# SerialComm.net
KiCad netlist of a schematic drawn in Altium Designer
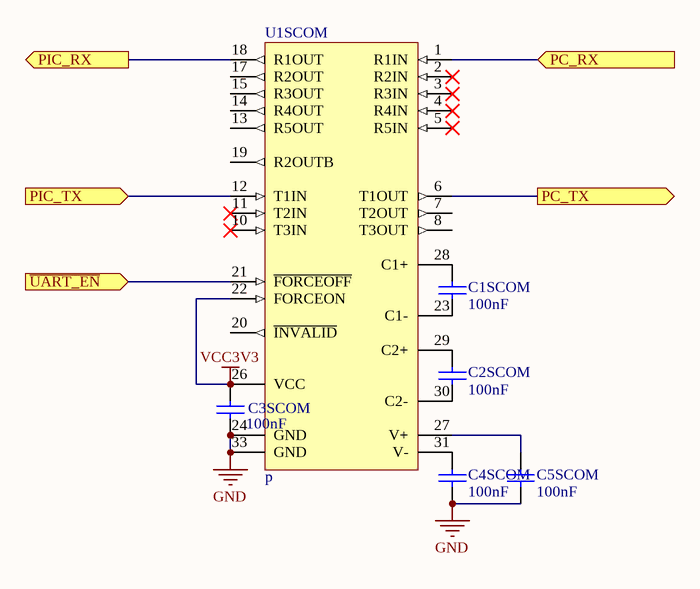
[diagram p0: SerialComm.SchDoc]

(export (version "E")
  (design (tool "Eeschema 10.0.6"))
  (components
    (comp (ref "C1SCOM")
      (value "100nF")
      (footprint "CC1608-0603")
      (description "Capacitor")
      (fields (field (name "MANUFACTURER") "Taiyo Yuden") (field (name "Comment") "UMK107BJ104KA-T"))
      (libsource (lib "Comp") (part "Cap"))
    )
    (comp (ref "C2SCOM")
      (value "100nF")
      (footprint "CC1608-0603")
      (description "Capacitor")
      (fields (field (name "MANUFACTURER") "Taiyo Yuden") (field (name "Comment") "UMK107BJ104KA-T"))
      (libsource (lib "Comp") (part "Cap"))
    )
    (comp (ref "C3SCOM")
      (value "100nF")
      (footprint "CC1608-0603")
      (description "Capacitor")
      (fields (field (name "MANUFACTURER") "Taiyo Yuden") (field (name "Comment") "UMK107BJ104KA-T"))
      (libsource (lib "Comp") (part "Cap"))
    )
    (comp (ref "C4SCOM")
      (value "100nF")
      (footprint "CC1608-0603")
      (description "Capacitor")
      (fields (field (name "MANUFACTURER") "Taiyo Yuden") (field (name "Comment") "UMK107BJ104KA-T"))
      (libsource (lib "Comp") (part "Cap"))
    )
    (comp (ref "C5SCOM")
      (value "100nF")
      (footprint "CC1608-0603")
      (description "Capacitor")
      (fields (field (name "MANUFACTURER") "Taiyo Yuden") (field (name "Comment") "UMK107BJ104KA-T"))
      (libsource (lib "Comp") (part "Cap"))
    )
    (comp (ref "U1SCOM")
      (value "p")
      (footprint "Footprints:QFN5X5-32")
      (description "RS232 Transceiver")
      (fields (field (name "MANUFACTURER") "Texas Instruments"))
      (libsource (lib "Comp") (part "MAX3243E_SMALL"))
    )
  )
  (nets
    (net (code "1") (name "/PC_RX") (class "Default")
      (node (ref "U1SCOM") (pin "1") (pinfunction "R1IN_1") (pintype "input"))
    )
    (net (code "2") (name "/PC_TX") (class "Default")
      (node (ref "U1SCOM") (pin "6") (pinfunction "T1OUT_6") (pintype "output"))
    )
    (net (code "3") (name "/PIC_RX") (class "Default")
      (node (ref "U1SCOM") (pin "18") (pinfunction "R1OUT_18") (pintype "output"))
    )
    (net (code "4") (name "/PIC_TX") (class "Default")
      (node (ref "U1SCOM") (pin "12") (pinfunction "T1IN_12") (pintype "input"))
    )
    (net (code "5") (name "/~{UART_EN}") (class "Default")
      (node (ref "U1SCOM") (pin "21") (pinfunction "~{FORCEOFF}_21") (pintype "input"))
    )
    (net (code "6") (name "GND") (class "Default")
      (node (ref "C3SCOM") (pin "2") (pinfunction "2_2") (pintype "passive"))
      (node (ref "C4SCOM") (pin "2") (pinfunction "2_2") (pintype "passive"))
      (node (ref "C5SCOM") (pin "2") (pinfunction "2_2") (pintype "passive"))
      (node (ref "U1SCOM") (pin "24") (pinfunction "GND_24") (pintype "power_in"))
      (node (ref "U1SCOM") (pin "33") (pinfunction "GND_33") (pintype "power_in"))
    )
    (net (code "7") (name "Net-(U1SCOM-C1+)") (class "Default")
      (node (ref "C1SCOM") (pin "1") (pinfunction "1_1") (pintype "passive"))
      (node (ref "U1SCOM") (pin "28") (pinfunction "C1+_28") (pintype "passive"))
    )
    (net (code "8") (name "Net-(U1SCOM-C1-)") (class "Default")
      (node (ref "C1SCOM") (pin "2") (pinfunction "2_2") (pintype "passive"))
      (node (ref "U1SCOM") (pin "23") (pinfunction "C1-_23") (pintype "passive"))
    )
    (net (code "9") (name "Net-(U1SCOM-C2+)") (class "Default")
      (node (ref "C2SCOM") (pin "1") (pinfunction "1_1") (pintype "passive"))
      (node (ref "U1SCOM") (pin "29") (pinfunction "C2+_29") (pintype "passive"))
    )
    (net (code "10") (name "Net-(U1SCOM-C2-)") (class "Default")
      (node (ref "C2SCOM") (pin "2") (pinfunction "2_2") (pintype "passive"))
      (node (ref "U1SCOM") (pin "30") (pinfunction "C2-_30") (pintype "passive"))
    )
    (net (code "11") (name "Net-(U1SCOM-V+)") (class "Default")
      (node (ref "C5SCOM") (pin "1") (pinfunction "1_1") (pintype "passive"))
      (node (ref "U1SCOM") (pin "27") (pinfunction "V+_27") (pintype "passive"))
    )
    (net (code "12") (name "Net-(U1SCOM-V-)") (class "Default")
      (node (ref "C4SCOM") (pin "1") (pinfunction "1_1") (pintype "passive"))
      (node (ref "U1SCOM") (pin "31") (pinfunction "V-_31") (pintype "passive"))
    )
    (net (code "13") (name "VCC3V3") (class "Default")
      (node (ref "C3SCOM") (pin "1") (pinfunction "1_1") (pintype "passive"))
      (node (ref "U1SCOM") (pin "22") (pinfunction "FORCEON_22") (pintype "input"))
      (node (ref "U1SCOM") (pin "26") (pinfunction "VCC_26") (pintype "power_in"))
    )
    (net (code "14") (name "unconnected-(U1SCOM-R2IN-Pad2)") (class "Default")
      (node (ref "U1SCOM") (pin "2") (pinfunction "R2IN_2") (pintype "input+no_connect"))
    )
    (net (code "15") (name "unconnected-(U1SCOM-R2OUT-Pad17)") (class "Default")
      (node (ref "U1SCOM") (pin "17") (pinfunction "R2OUT_17") (pintype "output"))
    )
    (net (code "16") (name "unconnected-(U1SCOM-R2OUTB-Pad19)") (class "Default")
      (node (ref "U1SCOM") (pin "19") (pinfunction "R2OUTB_19") (pintype "output"))
    )
    (net (code "17") (name "unconnected-(U1SCOM-R3IN-Pad3)") (class "Default")
      (node (ref "U1SCOM") (pin "3") (pinfunction "R3IN_3") (pintype "input+no_connect"))
    )
    (net (code "18") (name "unconnected-(U1SCOM-R3OUT-Pad15)") (class "Default")
      (node (ref "U1SCOM") (pin "15") (pinfunction "R3OUT_15") (pintype "output"))
    )
    (net (code "19") (name "unconnected-(U1SCOM-R4IN-Pad4)") (class "Default")
      (node (ref "U1SCOM") (pin "4") (pinfunction "R4IN_4") (pintype "input+no_connect"))
    )
    (net (code "20") (name "unconnected-(U1SCOM-R4OUT-Pad14)") (class "Default")
      (node (ref "U1SCOM") (pin "14") (pinfunction "R4OUT_14") (pintype "output"))
    )
    (net (code "21") (name "unconnected-(U1SCOM-R5IN-Pad5)") (class "Default")
      (node (ref "U1SCOM") (pin "5") (pinfunction "R5IN_5") (pintype "input+no_connect"))
    )
    (net (code "22") (name "unconnected-(U1SCOM-R5OUT-Pad13)") (class "Default")
      (node (ref "U1SCOM") (pin "13") (pinfunction "R5OUT_13") (pintype "output"))
    )
    (net (code "23") (name "unconnected-(U1SCOM-T2IN-Pad11)") (class "Default")
      (node (ref "U1SCOM") (pin "11") (pinfunction "T2IN_11") (pintype "input+no_connect"))
    )
    (net (code "24") (name "unconnected-(U1SCOM-T2OUT-Pad7)") (class "Default")
      (node (ref "U1SCOM") (pin "7") (pinfunction "T2OUT_7") (pintype "output"))
    )
    (net (code "25") (name "unconnected-(U1SCOM-T3IN-Pad10)") (class "Default")
      (node (ref "U1SCOM") (pin "10") (pinfunction "T3IN_10") (pintype "input+no_connect"))
    )
    (net (code "26") (name "unconnected-(U1SCOM-T3OUT-Pad8)") (class "Default")
      (node (ref "U1SCOM") (pin "8") (pinfunction "T3OUT_8") (pintype "output"))
    )
    (net (code "27") (name "unconnected-(U1SCOM-~{INVALID}-Pad20)") (class "Default")
      (node (ref "U1SCOM") (pin "20") (pinfunction "~{INVALID}_20") (pintype "output"))
    )
  )
)
